# EmergencyStop_-_RevA2.net
KiCad netlist of a schematic drawn in EAGLE
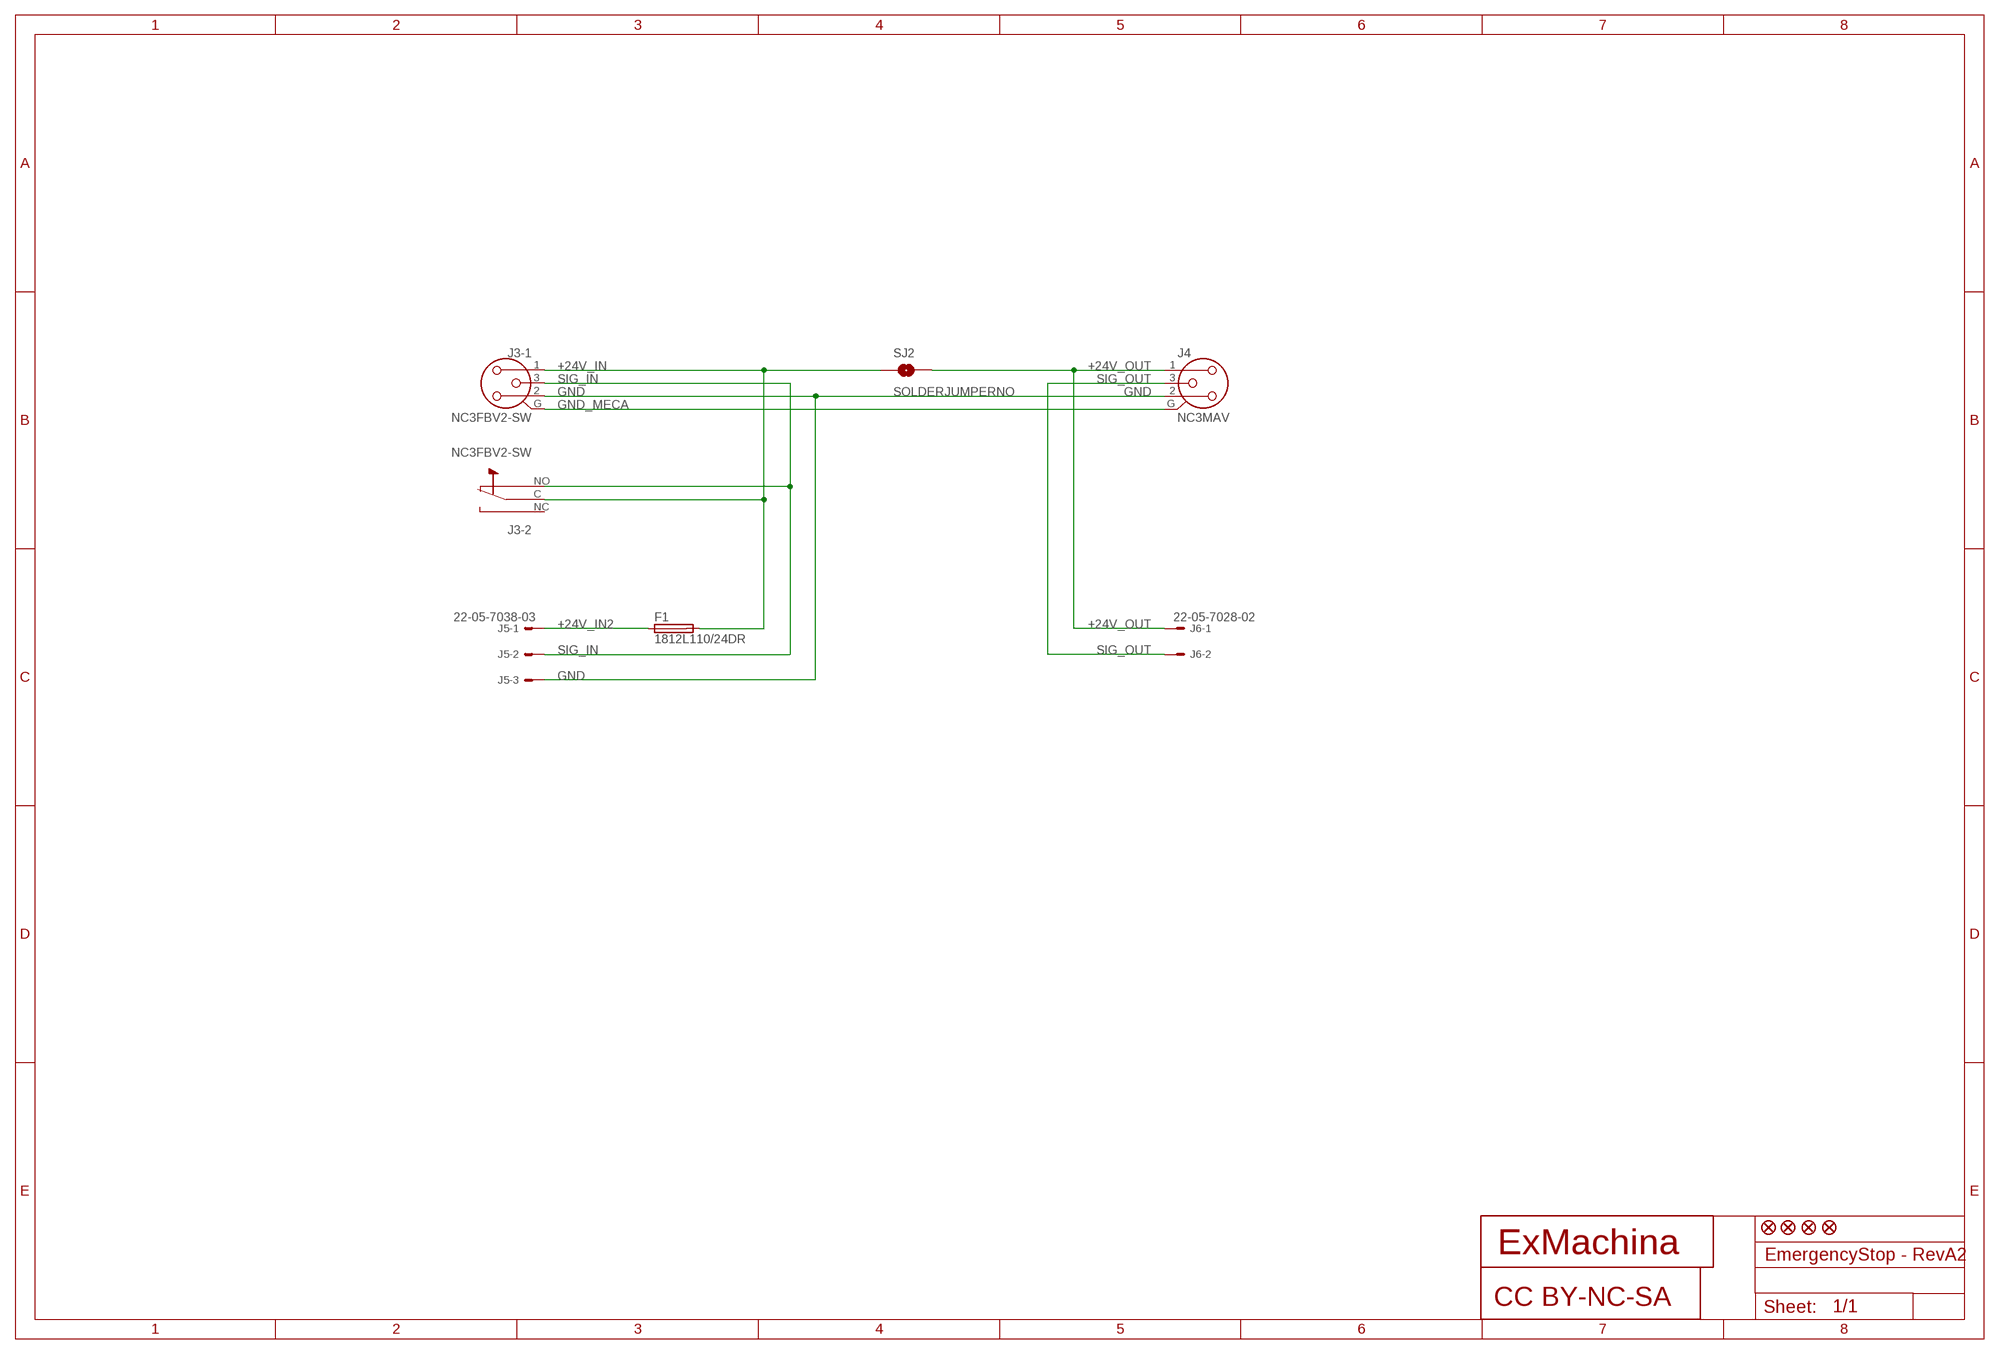
[diagram p0: schematic, sheet 1]

(export (version "E")
  (design (tool "Eeschema 10.0.6"))
  (components
    (comp (ref "CC1")
      (value "CC-BY-NC-SA")
      (footprint "eagle-import:CC-BY-NC-SA")
      (libsource (lib "eagle-import") (part "CC-BY-NC-SA"))
    )
    (comp (ref "F1")
      (value "1812L110/24DR")
      (footprint "eagle-import:LITTLEFUSE_SMD")
      (libsource (lib "eagle-import") (part "1812L110/24DR"))
    )
    (comp (ref "J3")
      (value "NC3FBV2-SW")
      (footprint "eagle-import:NC3FBV2-SW")
      (libsource (lib "eagle-import") (part "NC3?-SWFBV2"))
    )
    (comp (ref "J4")
      (value "NC3MAV")
      (footprint "eagle-import:NC3MAV")
      (fields (field (name "MF") "FARNELL"))
      (libsource (lib "eagle-import") (part "NC3MAV"))
    )
    (comp (ref "J5")
      (value "22-05-7038-03")
      (footprint "eagle-import:7395-03")
      (libsource (lib "eagle-import") (part "22-?-0305-7038"))
    )
    (comp (ref "J6")
      (value "22-05-7028-02")
      (footprint "eagle-import:7395-02")
      (libsource (lib "eagle-import") (part "22-?-0205-7028"))
    )
    (comp (ref "JP1")
      (value "FIDUCIAL1X2")
      (footprint "eagle-import:FIDUCIAL-1X2")
      (libsource (lib "eagle-import") (part "FIDUCIAL1X2"))
    )
    (comp (ref "JP2")
      (value "FIDUCIAL1X2")
      (footprint "eagle-import:FIDUCIAL-1X2")
      (libsource (lib "eagle-import") (part "FIDUCIAL1X2"))
    )
    (comp (ref "JP3")
      (value "FIDUCIAL1X2")
      (footprint "eagle-import:FIDUCIAL-1X2")
      (libsource (lib "eagle-import") (part "FIDUCIAL1X2"))
    )
    (comp (ref "JP4")
      (value "FIDUCIAL1X2")
      (footprint "eagle-import:FIDUCIAL-1X2")
      (libsource (lib "eagle-import") (part "FIDUCIAL1X2"))
    )
    (comp (ref "SJ2")
      (value "SOLDERJUMPERNO")
      (footprint "eagle-import:SJ_2S-NO")
      (libsource (lib "eagle-import") (part "SOLDERJUMPERNO"))
    )
    (comp (ref "T1")
      (value "EXMACHINA-LOGO-NAME")
      (footprint "eagle-import:EXM-LOGO-BASELINE")
      (libsource (lib "eagle-import") (part "EXMACHINA-LOGO-NAME"))
    )
  )
  (nets
    (net (code "1") (name "/+24V_IN") (class "Default")
      (node (ref "F1") (pin "2") (pinfunction "2_2") (pintype "passive"))
      (node (ref "J3") (pin "1") (pinfunction "1_1") (pintype "passive"))
      (node (ref "J3") (pin "C") (pinfunction "N_C") (pintype "passive"))
      (node (ref "SJ2") (pin "1") (pinfunction "1_1") (pintype "passive"))
    )
    (net (code "2") (name "/+24V_IN2") (class "Default")
      (node (ref "F1") (pin "1") (pinfunction "1_1") (pintype "passive"))
      (node (ref "J5") (pin "1") (pinfunction "S_1") (pintype "passive"))
    )
    (net (code "3") (name "/+24V_OUT") (class "Default")
      (node (ref "J4") (pin "1") (pinfunction "1_1") (pintype "passive"))
      (node (ref "J6") (pin "1") (pinfunction "S_1") (pintype "passive"))
      (node (ref "SJ2") (pin "2") (pinfunction "2_2") (pintype "passive"))
    )
    (net (code "4") (name "/GND") (class "Default")
      (node (ref "J3") (pin "2") (pinfunction "2_2") (pintype "passive"))
      (node (ref "J4") (pin "2") (pinfunction "2_2") (pintype "passive"))
      (node (ref "J5") (pin "3") (pinfunction "S_3") (pintype "passive"))
    )
    (net (code "5") (name "/GND_MECA") (class "Default")
      (node (ref "J3") (pin "G") (pinfunction "G_G") (pintype "passive"))
      (node (ref "J4") (pin "G") (pinfunction "G_G") (pintype "passive"))
    )
    (net (code "6") (name "/SIG_IN") (class "Default")
      (node (ref "J3") (pin "3") (pinfunction "3_3") (pintype "passive"))
      (node (ref "J3") (pin "NO") (pinfunction "NO_NO") (pintype "passive"))
      (node (ref "J5") (pin "2") (pinfunction "S_2") (pintype "passive"))
    )
    (net (code "7") (name "/SIG_OUT") (class "Default")
      (node (ref "J4") (pin "3") (pinfunction "3_3") (pintype "passive"))
      (node (ref "J6") (pin "2") (pinfunction "S_2") (pintype "passive"))
    )
    (net (code "8") (name "unconnected-(J3-PadNC)") (class "Default")
      (node (ref "J3") (pin "NC") (pinfunction "NC_NC") (pintype "passive"))
    )
  )
)
